# Hoja_Control.net
KiCad netlist of a schematic drawn in Altium Designer
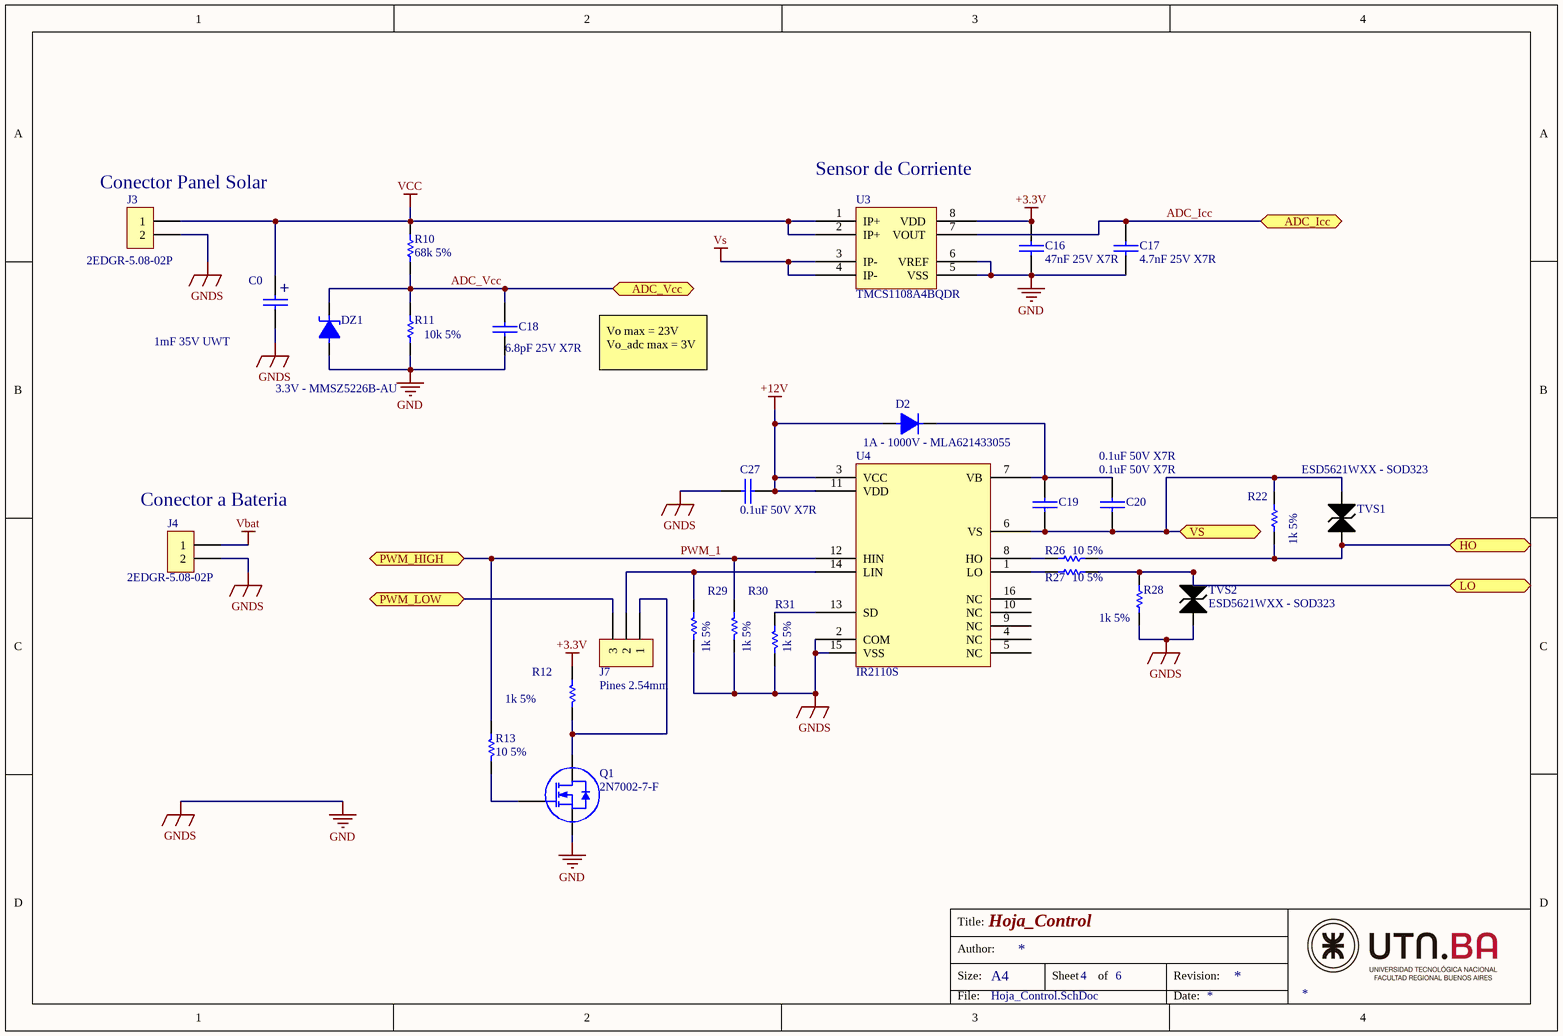
[diagram p0: Hoja_Control.SchDoc]

(export (version "E")
  (design (tool "Eeschema 10.0.6"))
  (components
    (comp (ref "C0")
      (value "1mF 35V UWT")
      (footprint "CAPSMD8x8.3")
      (libsource (lib "LIBEBAL") (part "CAPPOL"))
    )
    (comp (ref "C16")
      (value "47nF 25V X7R")
      (footprint "0805")
      (libsource (lib "Libreria_Casera") (part "CAP"))
    )
    (comp (ref "C17")
      (value "4.7nF 25V X7R")
      (footprint "0805")
      (libsource (lib "Libreria_Casera") (part "CAP"))
    )
    (comp (ref "C18")
      (value "6.8pF 25V X7R")
      (footprint "0805")
      (libsource (lib "Libreria_Casera") (part "CAP"))
    )
    (comp (ref "C19")
      (value "0.1uF 50V X7R")
      (footprint "0805")
      (description "CAP CER 0.1UF X7R 0805")
      (libsource (lib "Libreria_Casera") (part "CAP"))
    )
    (comp (ref "C20")
      (value "0.1uF 50V X7R")
      (footprint "0805")
      (description "CAP CER 0.1UF X7R 0805")
      (libsource (lib "Libreria_Casera") (part "CAP"))
    )
    (comp (ref "C27")
      (value "0.1uF 50V X7R")
      (footprint "0805")
      (description "CAP CER 0.1UF X7R 0805")
      (libsource (lib "Libreria_Casera") (part "CAP"))
    )
    (comp (ref "D2")
      (value "1A - 1000V - MLA621433055")
      (footprint "DO-214AC")
      (description "Diodos Estándar 1000 V 1A Montaje en superficie SMA")
      (libsource (lib "Libreria_Casera") (part "DIODO"))
    )
    (comp (ref "DZ1")
      (value "3.3V - MMSZ5226B-AU")
      (footprint "sod123")
      (libsource (lib "Libreria_Casera") (part "DIODO ZENER"))
    )
    (comp (ref "J3")
      (value "2EDGR-5.08-02P")
      (footprint "Bornera2_DegsonH")
      (libsource (lib "Libreria_Casera") (part "BORNERA 2"))
    )
    (comp (ref "J4")
      (value "2EDGR-5.08-02P")
      (footprint "Bornera2_DegsonH")
      (libsource (lib "Libreria_Casera") (part "BORNERA 2"))
    )
    (comp (ref "J7")
      (value "Pines 2.54mm")
      (footprint "SIP3")
      (libsource (lib "Libreria_Casera") (part "CON3"))
    )
    (comp (ref "Q1")
      (value "2N7002-7-F")
      (footprint "SOT23")
      (description "Canal N Montaje en superficie 60 V 115mA (Ta) 370mW (Ta) SOT-23-3")
      (libsource (lib "Libreria_Casera") (part "MOSFET N"))
    )
    (comp (ref "R10") (value "68k 5%") (footprint "0805") (libsource (lib "Libreria_Casera") (part "RES")))
    (comp (ref "R11") (value "10k 5%") (footprint "0805") (libsource (lib "Libreria_Casera") (part "RES")))
    (comp (ref "R12") (value "1k 5%") (footprint "0805") (libsource (lib "Libreria_Casera") (part "RES")))
    (comp (ref "R13") (value "10 5%") (footprint "0805") (libsource (lib "Libreria_Casera") (part "RES")))
    (comp (ref "R22") (value "1k 5%") (footprint "0805") (libsource (lib "Libreria_Casera") (part "RES")))
    (comp (ref "R26") (value "10 5%") (footprint "0805") (libsource (lib "Libreria_Casera") (part "RES")))
    (comp (ref "R27") (value "10 5%") (footprint "0805") (libsource (lib "Libreria_Casera") (part "RES")))
    (comp (ref "R28") (value "1k 5%") (footprint "0805") (libsource (lib "Libreria_Casera") (part "RES")))
    (comp (ref "R29") (value "1k 5%") (footprint "0805") (libsource (lib "Libreria_Casera") (part "RES")))
    (comp (ref "R30") (value "1k 5%") (footprint "0805") (libsource (lib "Libreria_Casera") (part "RES")))
    (comp (ref "R31") (value "1k 5%") (footprint "0805") (libsource (lib "Libreria_Casera") (part "RES")))
    (comp (ref "TVS1")
      (value "ESD5621WXX - SOD323")
      (footprint "SOD323")
      (libsource (lib "Libreria_Casera") (part "TVS"))
    )
    (comp (ref "TVS2")
      (value "ESD5621WXX - SOD323")
      (footprint "SOD323")
      (libsource (lib "Libreria_Casera") (part "TVS"))
    )
    (comp (ref "U3")
      (value "TMCS1108A4BQDR")
      (footprint "SOIC8")
      (description "Sensores de corriente 1 canal Efecto Hall Bidireccional 8-SOIC (ancho 0.154\", 3.90mm)")
      (libsource (lib "Libreria_Casera") (part "MLX91221KDC"))
    )
    (comp (ref "U4")
      (value "IR2110S")
      (footprint "SOIC16W")
      (description "Medio puente controladores de compuerta IC No inversor 14-DIP")
      (libsource (lib "Libreria_Casera") (part "IR2110 16"))
    )
  )
  (nets
    (net (code "1") (name "+3.3V") (class "Default")
      (node (ref "C16") (pin "1") (pinfunction "1_1") (pintype "passive"))
      (node (ref "R12") (pin "2") (pinfunction "2_2") (pintype "passive"))
      (node (ref "U3") (pin "8") (pinfunction "VDD_8") (pintype "passive"))
    )
    (net (code "2") (name "+12V") (class "Default")
      (node (ref "C27") (pin "1") (pinfunction "1_1") (pintype "passive"))
      (node (ref "D2") (pin "1") (pinfunction "1_1") (pintype "passive"))
      (node (ref "U4") (pin "11") (pinfunction "VDD_11") (pintype "passive"))
      (node (ref "U4") (pin "3") (pinfunction "VCC_3") (pintype "passive"))
    )
    (net (code "3") (name "/ADC_Icc") (class "Default")
      (node (ref "C17") (pin "1") (pinfunction "1_1") (pintype "passive"))
      (node (ref "U3") (pin "7") (pinfunction "VOUT_7") (pintype "passive"))
    )
    (net (code "4") (name "/ADC_Vcc") (class "Default")
      (node (ref "C18") (pin "1") (pinfunction "1_1") (pintype "passive"))
      (node (ref "DZ1") (pin "2") (pinfunction "2_2") (pintype "passive"))
      (node (ref "R10") (pin "1") (pinfunction "1_1") (pintype "passive"))
      (node (ref "R11") (pin "2") (pinfunction "2_2") (pintype "passive"))
    )
    (net (code "5") (name "/HO") (class "Default")
      (node (ref "R22") (pin "1") (pinfunction "1_1") (pintype "passive"))
      (node (ref "R26") (pin "2") (pinfunction "2_2") (pintype "passive"))
      (node (ref "TVS1") (pin "2") (pinfunction "2_2") (pintype "passive"))
    )
    (net (code "6") (name "/LO") (class "Default")
      (node (ref "R27") (pin "2") (pinfunction "2_2") (pintype "passive"))
      (node (ref "R28") (pin "2") (pinfunction "2_2") (pintype "passive"))
      (node (ref "TVS2") (pin "1") (pinfunction "1_1") (pintype "passive"))
    )
    (net (code "7") (name "/PWM_1") (class "Default")
      (node (ref "R13") (pin "2") (pinfunction "2_2") (pintype "passive"))
      (node (ref "R30") (pin "2") (pinfunction "2_2") (pintype "passive"))
      (node (ref "U4") (pin "12") (pinfunction "HIN_12") (pintype "passive"))
    )
    (net (code "8") (name "/PWM_LOW") (class "Default")
      (node (ref "J7") (pin "3") (pinfunction "3_3") (pintype "passive"))
    )
    (net (code "9") (name "/VS") (class "Default")
      (node (ref "C19") (pin "1") (pinfunction "1_1") (pintype "passive"))
      (node (ref "C20") (pin "1") (pinfunction "1_1") (pintype "passive"))
      (node (ref "R22") (pin "2") (pinfunction "2_2") (pintype "passive"))
      (node (ref "TVS1") (pin "1") (pinfunction "1_1") (pintype "passive"))
      (node (ref "U4") (pin "6") (pinfunction "VS_6") (pintype "passive"))
    )
    (net (code "10") (name "GND") (class "Default")
      (node (ref "C0") (pin "2") (pinfunction "2_2") (pintype "passive"))
      (node (ref "C16") (pin "2") (pinfunction "2_2") (pintype "passive"))
      (node (ref "C17") (pin "2") (pinfunction "2_2") (pintype "passive"))
      (node (ref "C18") (pin "2") (pinfunction "2_2") (pintype "passive"))
      (node (ref "C27") (pin "2") (pinfunction "2_2") (pintype "passive"))
      (node (ref "DZ1") (pin "1") (pinfunction "1_1") (pintype "passive"))
      (node (ref "J3") (pin "2") (pinfunction "2_2") (pintype "passive"))
      (node (ref "J4") (pin "2") (pinfunction "2_2") (pintype "passive"))
      (node (ref "Q1") (pin "3") (pinfunction "S_3") (pintype "passive"))
      (node (ref "R11") (pin "1") (pinfunction "1_1") (pintype "passive"))
      (node (ref "R28") (pin "1") (pinfunction "1_1") (pintype "passive"))
      (node (ref "R29") (pin "1") (pinfunction "1_1") (pintype "passive"))
      (node (ref "R30") (pin "1") (pinfunction "1_1") (pintype "passive"))
      (node (ref "R31") (pin "1") (pinfunction "1_1") (pintype "passive"))
      (node (ref "TVS2") (pin "2") (pinfunction "2_2") (pintype "passive"))
      (node (ref "U3") (pin "5") (pinfunction "VSS_5") (pintype "passive"))
      (node (ref "U3") (pin "6") (pinfunction "VREF_6") (pintype "passive"))
      (node (ref "U4") (pin "15") (pinfunction "VSS_15") (pintype "passive"))
      (node (ref "U4") (pin "2") (pinfunction "COM_2") (pintype "passive"))
    )
    (net (code "11") (name "Net-(Q1-D)") (class "Default")
      (node (ref "J7") (pin "1") (pinfunction "1_1") (pintype "passive"))
      (node (ref "Q1") (pin "2") (pinfunction "D_2") (pintype "passive"))
      (node (ref "R12") (pin "1") (pinfunction "1_1") (pintype "passive"))
    )
    (net (code "12") (name "Net-(Q1-G)") (class "Default")
      (node (ref "Q1") (pin "1") (pinfunction "G_1") (pintype "passive"))
      (node (ref "R13") (pin "1") (pinfunction "1_1") (pintype "passive"))
    )
    (net (code "13") (name "Net-(U4-HO)") (class "Default")
      (node (ref "R26") (pin "1") (pinfunction "1_1") (pintype "passive"))
      (node (ref "U4") (pin "8") (pinfunction "HO_8") (pintype "passive"))
    )
    (net (code "14") (name "Net-(U4-LIN)") (class "Default")
      (node (ref "J7") (pin "2") (pinfunction "2_2") (pintype "passive"))
      (node (ref "R29") (pin "2") (pinfunction "2_2") (pintype "passive"))
      (node (ref "U4") (pin "14") (pinfunction "LIN_14") (pintype "passive"))
    )
    (net (code "15") (name "Net-(U4-LO)") (class "Default")
      (node (ref "R27") (pin "1") (pinfunction "1_1") (pintype "passive"))
      (node (ref "U4") (pin "1") (pinfunction "LO_1") (pintype "passive"))
    )
    (net (code "16") (name "Net-(U4-SD)") (class "Default")
      (node (ref "R31") (pin "2") (pinfunction "2_2") (pintype "passive"))
      (node (ref "U4") (pin "13") (pinfunction "SD_13") (pintype "passive"))
    )
    (net (code "17") (name "Net-(U4-VB)") (class "Default")
      (node (ref "C19") (pin "2") (pinfunction "2_2") (pintype "passive"))
      (node (ref "C20") (pin "2") (pinfunction "2_2") (pintype "passive"))
      (node (ref "D2") (pin "2") (pinfunction "2_2") (pintype "passive"))
      (node (ref "U4") (pin "7") (pinfunction "VB_7") (pintype "passive"))
    )
    (net (code "18") (name "VCC") (class "Default")
      (node (ref "C0") (pin "1") (pinfunction "1_1") (pintype "passive"))
      (node (ref "J3") (pin "1") (pinfunction "1_1") (pintype "passive"))
      (node (ref "R10") (pin "2") (pinfunction "2_2") (pintype "passive"))
      (node (ref "U3") (pin "1") (pinfunction "IP+_1") (pintype "passive"))
      (node (ref "U3") (pin "2") (pinfunction "IP+_2") (pintype "passive"))
    )
    (net (code "19") (name "Vbat") (class "Default")
      (node (ref "J4") (pin "1") (pinfunction "1_1") (pintype "passive"))
    )
    (net (code "20") (name "Vs") (class "Default")
      (node (ref "U3") (pin "3") (pinfunction "IP-_3") (pintype "passive"))
      (node (ref "U3") (pin "4") (pinfunction "IP-_4") (pintype "passive"))
    )
    (net (code "21") (name "unconnected-(U4-NC-Pad4)") (class "Default")
      (node (ref "U4") (pin "4") (pinfunction "NC_4") (pintype "passive"))
    )
    (net (code "22") (name "unconnected-(U4-NC-Pad5)") (class "Default")
      (node (ref "U4") (pin "5") (pinfunction "NC_5") (pintype "passive"))
    )
    (net (code "23") (name "unconnected-(U4-NC-Pad9)") (class "Default")
      (node (ref "U4") (pin "9") (pinfunction "NC_9") (pintype "passive"))
    )
    (net (code "24") (name "unconnected-(U4-NC-Pad10)") (class "Default")
      (node (ref "U4") (pin "10") (pinfunction "NC_10") (pintype "passive"))
    )
    (net (code "25") (name "unconnected-(U4-NC-Pad16)") (class "Default")
      (node (ref "U4") (pin "16") (pinfunction "NC_16") (pintype "passive"))
    )
  )
)
